# project.net
KiCad netlist of a schematic drawn in Altium Designer
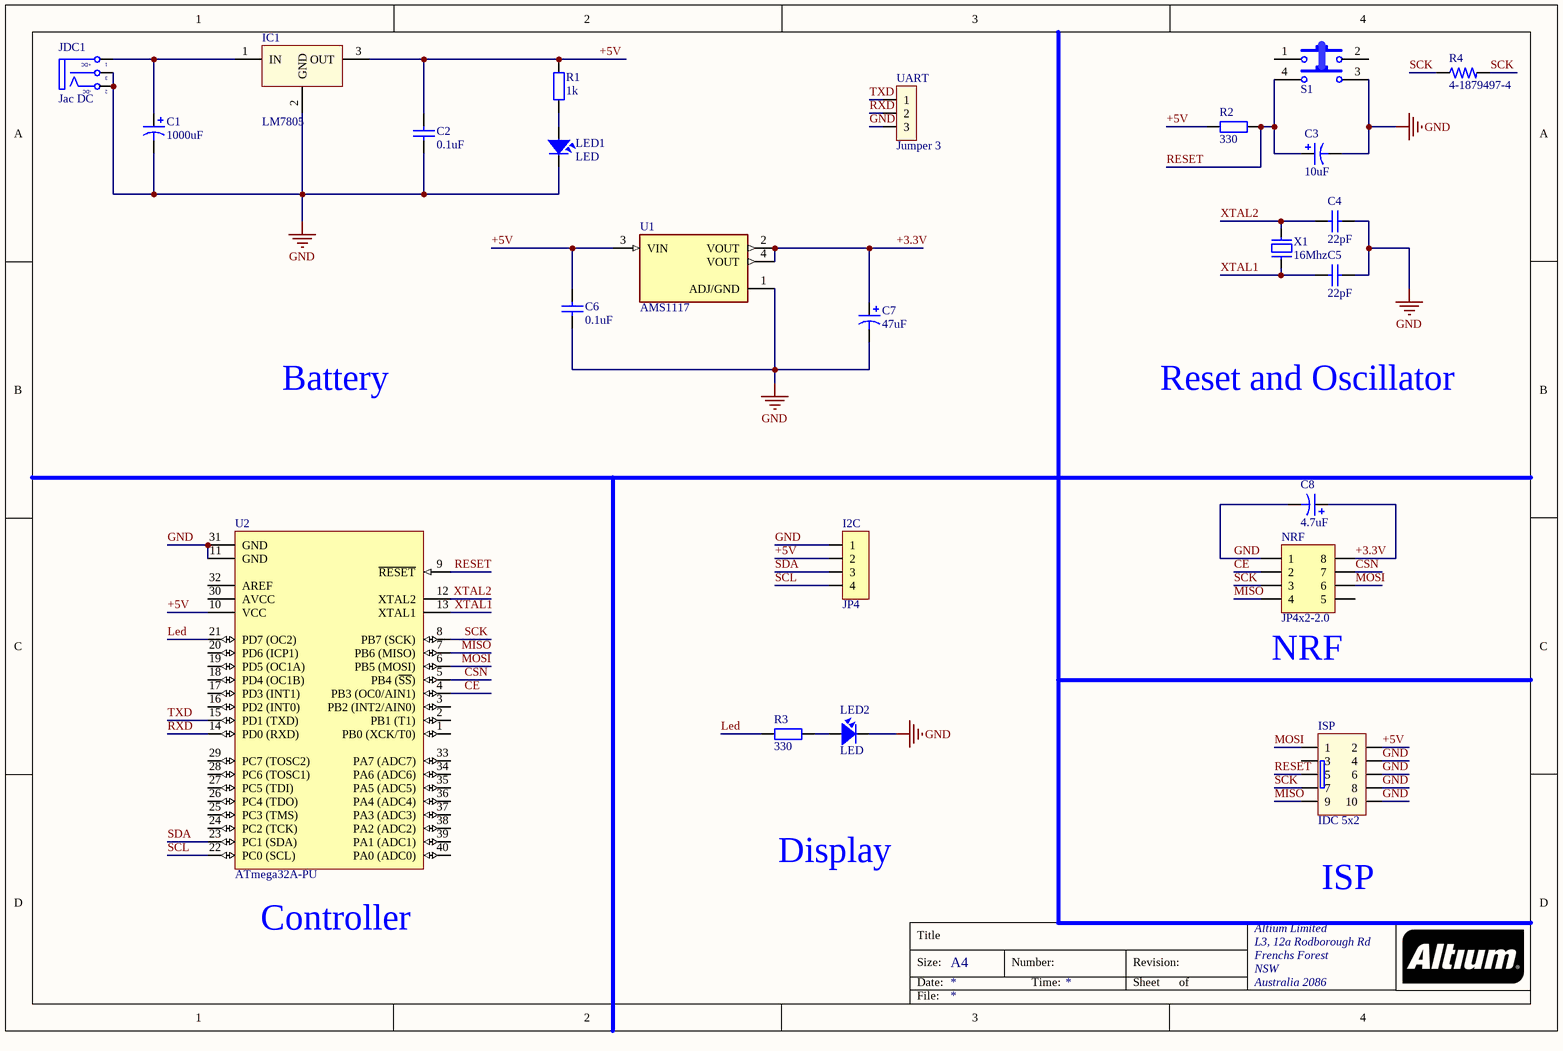
[diagram p0: project.SchDoc]

(export (version "E")
  (design (tool "Eeschema 10.0.6"))
  (components
    (comp (ref "C1")
      (value "1000uF")
      (footprint "C10mm")
      (description "Polarized Capacitor (Axial)")
      (fields (field (name "PUBLISHER") "Altium Limited"))
      (libsource (lib "My Library") (part "Cap Pol 8mm"))
    )
    (comp (ref "C2") (value "0.1uF") (footprint "C1206") (libsource (lib "My Library") (part "Cap SMD 1206")))
    (comp (ref "C3")
      (value "10uF")
      (footprint "C10mm")
      (description "Polarized Capacitor (Axial)")
      (fields (field (name "PUBLISHER") "Altium Limited"))
      (libsource (lib "My Library") (part "Cap Pol 8mm"))
    )
    (comp (ref "C4") (value "22pF") (footprint "C1206") (libsource (lib "My Library") (part "Cap SMD 1206")))
    (comp (ref "C5") (value "22pF") (footprint "C1206") (libsource (lib "My Library") (part "Cap SMD 1206")))
    (comp (ref "C6") (value "0.1uF") (footprint "C1206") (libsource (lib "My Library") (part "Cap SMD 1206")))
    (comp (ref "C7")
      (value "47uF")
      (footprint "C10mm")
      (description "Polarized Capacitor (Axial)")
      (fields (field (name "PUBLISHER") "Altium Limited"))
      (libsource (lib "My Library") (part "Cap Pol 8mm"))
    )
    (comp (ref "C8")
      (value "4.7uF")
      (footprint "C10mm")
      (description "Polarized Capacitor (Axial)")
      (fields (field (name "PUBLISHER") "Altium Limited"))
      (libsource (lib "My Library") (part "Cap Pol 8mm"))
    )
    (comp (ref "I2C")
      (value "JP4")
      (footprint "JP4-C1T")
      (description "WR-PHD 2.54 mm Angled Socket Header")
      (fields
        (field (name "MANUFACTURER") "Würth Elektronik eiSos GmbH")
        (field (name "PARTNO") "613004143121")
        (field (name "CREATED BY") "Karrer Zheng")
      )
      (libsource (lib "My Library") (part "JP4"))
    )
    (comp (ref "IC1")
      (value "LM7805")
      (footprint "QTO-220")
      (description "On ap +, from + 5 to + 24VDC")
      (libsource (lib "My Library") (part "LM78xx"))
    )
    (comp (ref "ISP") (value "IDC 5x2") (footprint "IDC10") (libsource (lib "My Library") (part "IDC 5X2")))
    (comp (ref "JDC1")
      (value "Jac DC")
      (footprint "DC-IN")
      (description "Jac DC input")
      (libsource (lib "My Library") (part "DCIN"))
    )
    (comp (ref "LED1")
      (value "LED")
      (footprint "LED-3")
      (description "LED Single colour Green and Red")
      (libsource (lib "My Library") (part "LED"))
    )
    (comp (ref "LED2")
      (value "LED")
      (footprint "LED-3")
      (description "LED Single colour Green and Red")
      (libsource (lib "My Library") (part "LED"))
    )
    (comp (ref "NRF")
      (value "JP4x2-2.0")
      (footprint "J4-C2T")
      (description "WR-PHD 2.00 mm Dual Pin Header")
      (fields
        (field (name "MANUFACTURER") "Würth Elektronik eiSos GmbH")
        (field (name "PARTNO") "62000821121")
        (field (name "CREATED BY") "Karrer Zheng")
      )
      (libsource (lib "My Library") (part "JP4x2-2.0"))
    )
    (comp (ref "R1")
      (value "1k")
      (footprint "R1/4W")
      (description "Resistor 1/4W")
      (libsource (lib "My Library") (part "R1/4W"))
    )
    (comp (ref "R2")
      (value "330")
      (footprint "R1/4W")
      (description "Resistor 1/4W")
      (libsource (lib "My Library") (part "R1/4W"))
    )
    (comp (ref "R3")
      (value "330")
      (footprint "R1/4W")
      (description "Resistor 1/4W")
      (libsource (lib "My Library") (part "R1/4W"))
    )
    (comp (ref "R4")
      (value "4-1879497-4")
      (footprint "RESC3115X65N")
      (description "CRGH1206 5% 62R 0.5W")
      (libsource (lib "4-1879497-4") (part "4-1879497-4"))
    )
    (comp (ref "S1")
      (value "SW-4P-S")
      (footprint "SW-4P-S")
      (description "Switch Small 4 Pin")
      (fields (field (name "PUBLISHER") "Altium Limited"))
      (libsource (lib "My Library") (part "SW-4PIN-SMALL"))
    )
    (comp (ref "U1")
      (value "AMS1117")
      (footprint "SOT229P700X180-4N")
      (description "UNO PLUS Arduino R3 Shield, Xbee Arduino IDE Wheeled Robotics Kit")
      (fields (field (name "MF") "Seeed Technology"))
      (libsource (lib "AMS1117") (part "AMS1117"))
    )
    (comp (ref "U2")
      (value "ATmega32A-PU")
      (footprint "DIP40/W0.6")
      (description "8-Bit AVR Microcontroller with 32K Bytes of In-System Programmable Flash Memory")
      (fields (field (name "PUBLISHER") "Altium Limited"))
      (libsource (lib "My Library") (part "ATmega32A-PU"))
    )
    (comp (ref "UART") (value "Jumper 3") (footprint "JP3") (libsource (lib "My Library") (part "JP3")))
    (comp (ref "X1")
      (value "16Mhz")
      (footprint "XT2")
      (description "Crystal For all Crystal 2pin.")
      (libsource (lib "My Library") (part "XT2"))
    )
  )
  (nets
    (net (code "1") (name "/+3.3V") (class "Default")
      (node (ref "C7") (pin "1") (pinfunction "1_1") (pintype "passive"))
      (node (ref "C8") (pin "1") (pinfunction "1_1") (pintype "passive"))
      (node (ref "NRF") (pin "8") (pinfunction "8_8") (pintype "passive"))
      (node (ref "U1") (pin "2") (pinfunction "VOUT_2") (pintype "output"))
      (node (ref "U1") (pin "4") (pinfunction "VOUT_4") (pintype "output"))
    )
    (net (code "2") (name "/+5V") (class "Default")
      (node (ref "C2") (pin "2") (pinfunction "2_2") (pintype "passive"))
      (node (ref "C6") (pin "2") (pinfunction "2_2") (pintype "passive"))
      (node (ref "I2C") (pin "2") (pinfunction "2_2") (pintype "passive"))
      (node (ref "IC1") (pin "3") (pinfunction "OUT_3") (pintype "passive"))
      (node (ref "ISP") (pin "2") (pinfunction "2_2") (pintype "passive"))
      (node (ref "R1") (pin "1") (pinfunction "1_1") (pintype "passive"))
      (node (ref "R2") (pin "2") (pinfunction "2_2") (pintype "passive"))
      (node (ref "U1") (pin "3") (pinfunction "VIN_3") (pintype "input"))
      (node (ref "U2") (pin "10") (pinfunction "VCC_10") (pintype "power_in"))
    )
    (net (code "3") (name "/CE") (class "Default")
      (node (ref "NRF") (pin "2") (pinfunction "2_2") (pintype "passive"))
      (node (ref "U2") (pin "4") (pinfunction "PB3_(OC0/AIN1)_4") (pintype "bidirectional"))
    )
    (net (code "4") (name "/CSN") (class "Default")
      (node (ref "NRF") (pin "7") (pinfunction "7_7") (pintype "passive"))
      (node (ref "U2") (pin "5") (pinfunction "PB4_(~{SS})_5") (pintype "bidirectional"))
    )
    (net (code "5") (name "/Led") (class "Default")
      (node (ref "R3") (pin "1") (pinfunction "1_1") (pintype "passive"))
      (node (ref "U2") (pin "21") (pinfunction "PD7_(OC2)_21") (pintype "bidirectional"))
    )
    (net (code "6") (name "/MISO") (class "Default")
      (node (ref "ISP") (pin "9") (pinfunction "9_9") (pintype "passive"))
      (node (ref "NRF") (pin "4") (pinfunction "4_4") (pintype "passive"))
      (node (ref "U2") (pin "7") (pinfunction "PB6_(MISO)_7") (pintype "bidirectional"))
    )
    (net (code "7") (name "/MOSI") (class "Default")
      (node (ref "ISP") (pin "1") (pinfunction "1_1") (pintype "passive"))
      (node (ref "NRF") (pin "6") (pinfunction "6_6") (pintype "passive"))
      (node (ref "U2") (pin "6") (pinfunction "PB5_(MOSI)_6") (pintype "bidirectional"))
    )
    (net (code "8") (name "/RESET") (class "Default")
      (node (ref "C3") (pin "1") (pinfunction "1_1") (pintype "passive"))
      (node (ref "ISP") (pin "5") (pinfunction "5_5") (pintype "passive"))
      (node (ref "R2") (pin "1") (pinfunction "1_1") (pintype "passive"))
      (node (ref "S1") (pin "4") (pinfunction "4_4") (pintype "passive"))
      (node (ref "U2") (pin "9") (pinfunction "~{RESET}_9") (pintype "input"))
    )
    (net (code "9") (name "/RXD") (class "Default")
      (node (ref "U2") (pin "14") (pinfunction "PD0_(RXD)_14") (pintype "bidirectional"))
      (node (ref "UART") (pin "2") (pinfunction "2_2") (pintype "passive"))
    )
    (net (code "10") (name "/SCK") (class "Default")
      (node (ref "ISP") (pin "7") (pinfunction "7_7") (pintype "passive"))
      (node (ref "NRF") (pin "3") (pinfunction "3_3") (pintype "passive"))
      (node (ref "R4") (pin "1") (pinfunction "1_1") (pintype "passive"))
      (node (ref "R4") (pin "2") (pinfunction "2_2") (pintype "passive"))
      (node (ref "U2") (pin "8") (pinfunction "PB7_(SCK)_8") (pintype "bidirectional"))
    )
    (net (code "11") (name "/SCL") (class "Default")
      (node (ref "I2C") (pin "4") (pinfunction "4_4") (pintype "passive"))
      (node (ref "U2") (pin "22") (pinfunction "PC0_(SCL)_22") (pintype "bidirectional"))
    )
    (net (code "12") (name "/SDA") (class "Default")
      (node (ref "I2C") (pin "3") (pinfunction "3_3") (pintype "passive"))
      (node (ref "U2") (pin "23") (pinfunction "PC1_(SDA)_23") (pintype "bidirectional"))
    )
    (net (code "13") (name "/TXD") (class "Default")
      (node (ref "U2") (pin "15") (pinfunction "PD1_(TXD)_15") (pintype "bidirectional"))
      (node (ref "UART") (pin "1") (pinfunction "1_1") (pintype "passive"))
    )
    (net (code "14") (name "/XTAL1") (class "Default")
      (node (ref "C5") (pin "1") (pinfunction "1_1") (pintype "passive"))
      (node (ref "U2") (pin "13") (pinfunction "XTAL1_13") (pintype "passive"))
      (node (ref "X1") (pin "1") (pinfunction "1_1") (pintype "passive"))
    )
    (net (code "15") (name "/XTAL2") (class "Default")
      (node (ref "C4") (pin "2") (pinfunction "2_2") (pintype "passive"))
      (node (ref "U2") (pin "12") (pinfunction "XTAL2_12") (pintype "passive"))
      (node (ref "X1") (pin "2") (pinfunction "2_2") (pintype "passive"))
    )
    (net (code "16") (name "GND") (class "Default")
      (node (ref "C1") (pin "2") (pinfunction "2_2") (pintype "passive"))
      (node (ref "C2") (pin "1") (pinfunction "1_1") (pintype "passive"))
      (node (ref "C3") (pin "2") (pinfunction "2_2") (pintype "passive"))
      (node (ref "C4") (pin "1") (pinfunction "1_1") (pintype "passive"))
      (node (ref "C5") (pin "2") (pinfunction "2_2") (pintype "passive"))
      (node (ref "C6") (pin "1") (pinfunction "1_1") (pintype "passive"))
      (node (ref "C7") (pin "2") (pinfunction "2_2") (pintype "passive"))
      (node (ref "C8") (pin "2") (pinfunction "2_2") (pintype "passive"))
      (node (ref "I2C") (pin "1") (pinfunction "1_1") (pintype "passive"))
      (node (ref "IC1") (pin "2") (pinfunction "GND_2") (pintype "passive"))
      (node (ref "ISP") (pin "10") (pinfunction "10_10") (pintype "passive"))
      (node (ref "ISP") (pin "4") (pinfunction "4_4") (pintype "passive"))
      (node (ref "ISP") (pin "6") (pinfunction "6_6") (pintype "passive"))
      (node (ref "ISP") (pin "8") (pinfunction "8_8") (pintype "passive"))
      (node (ref "JDC1") (pin "2") (pinfunction "TN_2") (pintype "passive"))
      (node (ref "JDC1") (pin "3") (pinfunction "S_3") (pintype "power_in"))
      (node (ref "LED1") (pin "2") (pinfunction "2_2") (pintype "passive"))
      (node (ref "LED2") (pin "2") (pinfunction "2_2") (pintype "passive"))
      (node (ref "NRF") (pin "1") (pinfunction "1_1") (pintype "passive"))
      (node (ref "S1") (pin "3") (pinfunction "3_3") (pintype "passive"))
      (node (ref "U1") (pin "1") (pinfunction "ADJ/GND_1") (pintype "power_in"))
      (node (ref "U2") (pin "11") (pinfunction "GND_11") (pintype "power_in"))
      (node (ref "U2") (pin "31") (pinfunction "GND_31") (pintype "power_in"))
      (node (ref "UART") (pin "3") (pinfunction "3_3") (pintype "passive"))
    )
    (net (code "17") (name "Net-(IC1-IN)") (class "Default")
      (node (ref "C1") (pin "1") (pinfunction "1_1") (pintype "passive"))
      (node (ref "IC1") (pin "1") (pinfunction "IN_1") (pintype "passive"))
      (node (ref "JDC1") (pin "1") (pinfunction "T_1") (pintype "passive"))
    )
    (net (code "18") (name "Net-(LED1-Pad1)") (class "Default")
      (node (ref "LED1") (pin "1") (pinfunction "1_1") (pintype "passive"))
      (node (ref "R1") (pin "2") (pinfunction "2_2") (pintype "passive"))
    )
    (net (code "19") (name "Net-(LED2-Pad1)") (class "Default")
      (node (ref "LED2") (pin "1") (pinfunction "1_1") (pintype "passive"))
      (node (ref "R3") (pin "2") (pinfunction "2_2") (pintype "passive"))
    )
    (net (code "20") (name "unconnected-(ISP-Pad3)") (class "Default")
      (node (ref "ISP") (pin "3") (pinfunction "3_3") (pintype "passive"))
    )
    (net (code "21") (name "unconnected-(NRF-Pad5)") (class "Default")
      (node (ref "NRF") (pin "5") (pinfunction "5_5") (pintype "passive"))
    )
    (net (code "22") (name "unconnected-(S1-Pad1)") (class "Default")
      (node (ref "S1") (pin "1") (pinfunction "1_1") (pintype "passive"))
    )
    (net (code "23") (name "unconnected-(S1-Pad2)") (class "Default")
      (node (ref "S1") (pin "2") (pinfunction "2_2") (pintype "passive"))
    )
    (net (code "24") (name "unconnected-(U2-AREF-Pad32)") (class "Default")
      (node (ref "U2") (pin "32") (pinfunction "AREF_32") (pintype "power_in"))
    )
    (net (code "25") (name "unconnected-(U2-AVCC-Pad30)") (class "Default")
      (node (ref "U2") (pin "30") (pinfunction "AVCC_30") (pintype "power_in"))
    )
    (net (code "26") (name "unconnected-(U2-PA0_(ADC0)-Pad40)") (class "Default")
      (node (ref "U2") (pin "40") (pinfunction "PA0_(ADC0)_40") (pintype "bidirectional"))
    )
    (net (code "27") (name "unconnected-(U2-PA1_(ADC1)-Pad39)") (class "Default")
      (node (ref "U2") (pin "39") (pinfunction "PA1_(ADC1)_39") (pintype "bidirectional"))
    )
    (net (code "28") (name "unconnected-(U2-PA2_(ADC2)-Pad38)") (class "Default")
      (node (ref "U2") (pin "38") (pinfunction "PA2_(ADC2)_38") (pintype "bidirectional"))
    )
    (net (code "29") (name "unconnected-(U2-PA3_(ADC3)-Pad37)") (class "Default")
      (node (ref "U2") (pin "37") (pinfunction "PA3_(ADC3)_37") (pintype "bidirectional"))
    )
    (net (code "30") (name "unconnected-(U2-PA4_(ADC4)-Pad36)") (class "Default")
      (node (ref "U2") (pin "36") (pinfunction "PA4_(ADC4)_36") (pintype "bidirectional"))
    )
    (net (code "31") (name "unconnected-(U2-PA5_(ADC5)-Pad35)") (class "Default")
      (node (ref "U2") (pin "35") (pinfunction "PA5_(ADC5)_35") (pintype "bidirectional"))
    )
    (net (code "32") (name "unconnected-(U2-PA6_(ADC6)-Pad34)") (class "Default")
      (node (ref "U2") (pin "34") (pinfunction "PA6_(ADC6)_34") (pintype "bidirectional"))
    )
    (net (code "33") (name "unconnected-(U2-PA7_(ADC7)-Pad33)") (class "Default")
      (node (ref "U2") (pin "33") (pinfunction "PA7_(ADC7)_33") (pintype "bidirectional"))
    )
    (net (code "34") (name "unconnected-(U2-PB0_(XCK{slash}T0)-Pad1)") (class "Default")
      (node (ref "U2") (pin "1") (pinfunction "PB0_(XCK/T0)_1") (pintype "bidirectional"))
    )
    (net (code "35") (name "unconnected-(U2-PB1_(T1)-Pad2)") (class "Default")
      (node (ref "U2") (pin "2") (pinfunction "PB1_(T1)_2") (pintype "bidirectional"))
    )
    (net (code "36") (name "unconnected-(U2-PB2_(INT2{slash}AIN0)-Pad3)") (class "Default")
      (node (ref "U2") (pin "3") (pinfunction "PB2_(INT2/AIN0)_3") (pintype "bidirectional"))
    )
    (net (code "37") (name "unconnected-(U2-PC2_(TCK)-Pad24)") (class "Default")
      (node (ref "U2") (pin "24") (pinfunction "PC2_(TCK)_24") (pintype "bidirectional"))
    )
    (net (code "38") (name "unconnected-(U2-PC3_(TMS)-Pad25)") (class "Default")
      (node (ref "U2") (pin "25") (pinfunction "PC3_(TMS)_25") (pintype "bidirectional"))
    )
    (net (code "39") (name "unconnected-(U2-PC4_(TDO)-Pad26)") (class "Default")
      (node (ref "U2") (pin "26") (pinfunction "PC4_(TDO)_26") (pintype "bidirectional"))
    )
    (net (code "40") (name "unconnected-(U2-PC5_(TDI)-Pad27)") (class "Default")
      (node (ref "U2") (pin "27") (pinfunction "PC5_(TDI)_27") (pintype "bidirectional"))
    )
    (net (code "41") (name "unconnected-(U2-PC6_(TOSC1)-Pad28)") (class "Default")
      (node (ref "U2") (pin "28") (pinfunction "PC6_(TOSC1)_28") (pintype "bidirectional"))
    )
    (net (code "42") (name "unconnected-(U2-PC7_(TOSC2)-Pad29)") (class "Default")
      (node (ref "U2") (pin "29") (pinfunction "PC7_(TOSC2)_29") (pintype "bidirectional"))
    )
    (net (code "43") (name "unconnected-(U2-PD2_(INT0)-Pad16)") (class "Default")
      (node (ref "U2") (pin "16") (pinfunction "PD2_(INT0)_16") (pintype "bidirectional"))
    )
    (net (code "44") (name "unconnected-(U2-PD3_(INT1)-Pad17)") (class "Default")
      (node (ref "U2") (pin "17") (pinfunction "PD3_(INT1)_17") (pintype "bidirectional"))
    )
    (net (code "45") (name "unconnected-(U2-PD4_(OC1B)-Pad18)") (class "Default")
      (node (ref "U2") (pin "18") (pinfunction "PD4_(OC1B)_18") (pintype "bidirectional"))
    )
    (net (code "46") (name "unconnected-(U2-PD5_(OC1A)-Pad19)") (class "Default")
      (node (ref "U2") (pin "19") (pinfunction "PD5_(OC1A)_19") (pintype "bidirectional"))
    )
    (net (code "47") (name "unconnected-(U2-PD6_(ICP1)-Pad20)") (class "Default")
      (node (ref "U2") (pin "20") (pinfunction "PD6_(ICP1)_20") (pintype "bidirectional"))
    )
  )
)
